# Sheet_3_nizovie.net
KiCad netlist of a schematic drawn in Altium Designer
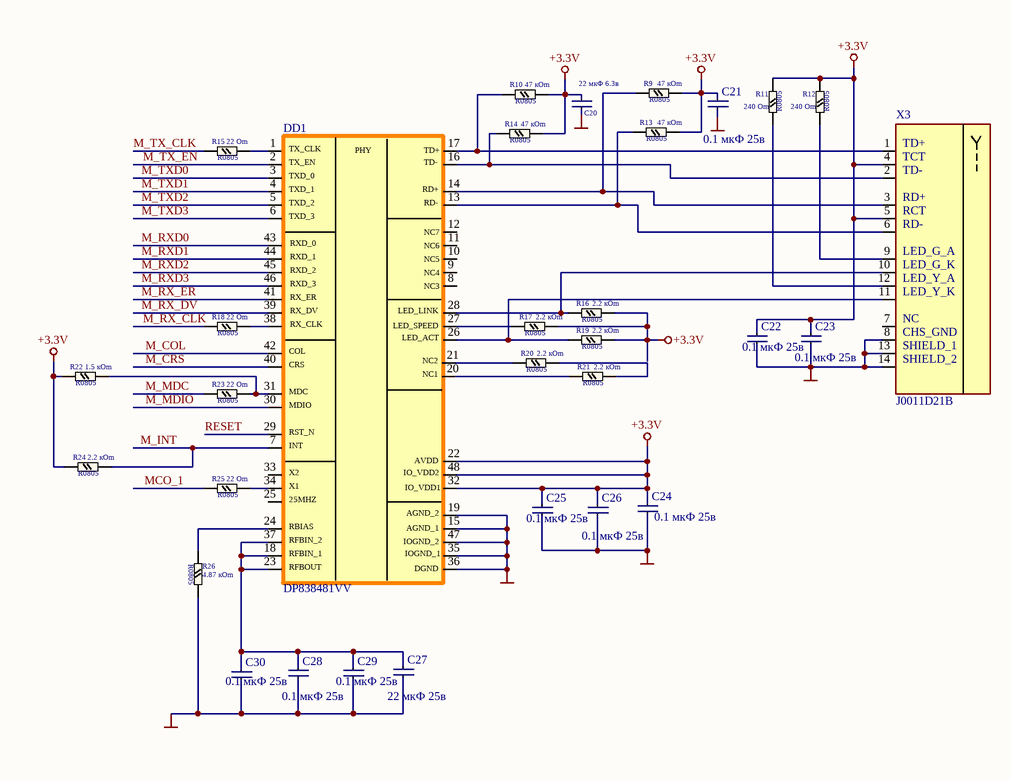
[diagram p0: Sheet_3_nizovie.SchDoc]

(export (version "E")
  (design (tool "Eeschema 10.0.6"))
  (components
    (comp (ref "C20")
      (value "22 мкФ 6.3в")
      (footprint "FP_0805")
      (libsource (lib "Schlib_nizovie") (part "C0805"))
    )
    (comp (ref "C21")
      (value "0.1 мкФ 25в")
      (footprint "FP_0805")
      (libsource (lib "Schlib_nizovie") (part "C0805"))
    )
    (comp (ref "C22")
      (value "0.1 мкФ 25в")
      (footprint "FP_0805")
      (libsource (lib "Schlib_nizovie") (part "C0805"))
    )
    (comp (ref "C23")
      (value "0.1 мкФ 25в")
      (footprint "FP_0805")
      (libsource (lib "Schlib_nizovie") (part "C0805"))
    )
    (comp (ref "C24")
      (value "0.1 мкФ 25в")
      (footprint "FP_0805")
      (libsource (lib "Schlib_nizovie") (part "C0805"))
    )
    (comp (ref "C25")
      (value "0.1 мкФ 25в")
      (footprint "FP_0805")
      (libsource (lib "Schlib_nizovie") (part "C0805"))
    )
    (comp (ref "C26")
      (value "0.1 мкФ 25в")
      (footprint "FP_0805")
      (libsource (lib "Schlib_nizovie") (part "C0805"))
    )
    (comp (ref "C27")
      (value "22 мкФ 25в")
      (footprint "FP_0805")
      (libsource (lib "Schlib_nizovie") (part "C0805"))
    )
    (comp (ref "C28")
      (value "0.1 мкФ 25в")
      (footprint "FP_0805")
      (libsource (lib "Schlib_nizovie") (part "C0805"))
    )
    (comp (ref "C29")
      (value "0.1 мкФ 25в")
      (footprint "FP_0805")
      (libsource (lib "Schlib_nizovie") (part "C0805"))
    )
    (comp (ref "C30")
      (value "0.1 мкФ 25в")
      (footprint "FP_0805")
      (libsource (lib "Schlib_nizovie") (part "C0805"))
    )
    (comp (ref "DD1")
      (value "DP838481VV")
      (footprint "TSQFP50P905X905X140-48N")
      (libsource (lib "Schlib_nizovie") (part "DP838481VV"))
    )
    (comp (ref "R9") (value "47 êÎm") (footprint "FP_0805") (libsource (lib "Schlib_nizovie") (part "R0805")))
    (comp (ref "R10")
      (value "47 êÎm")
      (footprint "FP_0805")
      (libsource (lib "Schlib_nizovie") (part "R0805"))
    )
    (comp (ref "R11") (value "240 Îm") (footprint "FP_0805") (libsource (lib "") (part "R0805_1")))
    (comp (ref "R12") (value "240 Îm") (footprint "FP_0805") (libsource (lib "") (part "R0805_1")))
    (comp (ref "R13")
      (value "47 êÎm")
      (footprint "FP_0805")
      (libsource (lib "Schlib_nizovie") (part "R0805"))
    )
    (comp (ref "R14")
      (value "47 êÎm")
      (footprint "FP_0805")
      (libsource (lib "Schlib_nizovie") (part "R0805"))
    )
    (comp (ref "R15") (value "22 Îm") (footprint "FP_0805") (libsource (lib "Schlib_nizovie") (part "R0805")))
    (comp (ref "R16")
      (value "2.2 êÎm")
      (footprint "FP_0805")
      (libsource (lib "Schlib_nizovie") (part "R0805"))
    )
    (comp (ref "R17")
      (value "2.2 êÎm")
      (footprint "FP_0805")
      (libsource (lib "Schlib_nizovie") (part "R0805"))
    )
    (comp (ref "R18") (value "22 Îm") (footprint "FP_0805") (libsource (lib "Schlib_nizovie") (part "R0805")))
    (comp (ref "R19")
      (value "2.2 êÎm")
      (footprint "FP_0805")
      (libsource (lib "Schlib_nizovie") (part "R0805"))
    )
    (comp (ref "R20")
      (value "2.2 êÎm")
      (footprint "FP_0805")
      (libsource (lib "Schlib_nizovie") (part "R0805"))
    )
    (comp (ref "R21")
      (value "2.2 êÎm")
      (footprint "FP_0805")
      (libsource (lib "Schlib_nizovie") (part "R0805"))
    )
    (comp (ref "R22")
      (value "1.5 êÎm")
      (footprint "FP_0805")
      (libsource (lib "Schlib_nizovie") (part "R0805"))
    )
    (comp (ref "R23") (value "22 Îm") (footprint "FP_0805") (libsource (lib "Schlib_nizovie") (part "R0805")))
    (comp (ref "R24")
      (value "2.2 êÎm")
      (footprint "FP_0805")
      (libsource (lib "Schlib_nizovie") (part "R0805"))
    )
    (comp (ref "R25") (value "22 Îm") (footprint "FP_0805") (libsource (lib "Schlib_nizovie") (part "R0805")))
    (comp (ref "R26") (value "4.87 êÎm") (footprint "FP_0805") (libsource (lib "") (part "R0805_2")))
    (comp (ref "X3")
      (value "J0011D21B")
      (footprint "J0006D21BNL")
      (libsource (lib "Schlib_nizovie") (part "J0011D21B"))
    )
  )
  (nets
    (net (code "1") (name "+3.3V") (class "Default")
      (node (ref "C20") (pin "2") (pinfunction "2_2") (pintype "passive"))
      (node (ref "C21") (pin "2") (pinfunction "2_2") (pintype "passive"))
      (node (ref "C22") (pin "2") (pinfunction "2_2") (pintype "passive"))
      (node (ref "C23") (pin "2") (pinfunction "2_2") (pintype "passive"))
      (node (ref "C24") (pin "2") (pinfunction "2_2") (pintype "passive"))
      (node (ref "C25") (pin "2") (pinfunction "2_2") (pintype "passive"))
      (node (ref "C26") (pin "2") (pinfunction "2_2") (pintype "passive"))
      (node (ref "DD1") (pin "22") (pinfunction "22_22") (pintype "passive"))
      (node (ref "DD1") (pin "32") (pinfunction "32_32") (pintype "passive"))
      (node (ref "DD1") (pin "48") (pinfunction "48_48") (pintype "passive"))
      (node (ref "R10") (pin "2") (pinfunction "2_2") (pintype "passive"))
      (node (ref "R11") (pin "2") (pinfunction "2_2") (pintype "passive"))
      (node (ref "R12") (pin "2") (pinfunction "2_2") (pintype "passive"))
      (node (ref "R13") (pin "2") (pinfunction "2_2") (pintype "passive"))
      (node (ref "R14") (pin "2") (pinfunction "2_2") (pintype "passive"))
      (node (ref "R16") (pin "2") (pinfunction "2_2") (pintype "passive"))
      (node (ref "R17") (pin "2") (pinfunction "2_2") (pintype "passive"))
      (node (ref "R19") (pin "2") (pinfunction "2_2") (pintype "passive"))
      (node (ref "R22") (pin "1") (pinfunction "1_1") (pintype "passive"))
      (node (ref "R24") (pin "1") (pinfunction "1_1") (pintype "passive"))
      (node (ref "R9") (pin "2") (pinfunction "2_2") (pintype "passive"))
      (node (ref "X3") (pin "4") (pinfunction "4_4") (pintype "passive"))
      (node (ref "X3") (pin "5") (pinfunction "5_5") (pintype "passive"))
    )
    (net (code "2") (name "/MCO_1") (class "Default")
      (node (ref "R25") (pin "1") (pinfunction "1_1") (pintype "passive"))
    )
    (net (code "3") (name "/M_COL") (class "Default")
      (node (ref "DD1") (pin "42") (pinfunction "42_42") (pintype "passive"))
    )
    (net (code "4") (name "/M_CRS") (class "Default")
      (node (ref "DD1") (pin "40") (pinfunction "40_40") (pintype "passive"))
    )
    (net (code "5") (name "/M_INT") (class "Default")
      (node (ref "DD1") (pin "7") (pinfunction "7_7") (pintype "passive"))
      (node (ref "R24") (pin "2") (pinfunction "2_2") (pintype "passive"))
    )
    (net (code "6") (name "/M_MDC") (class "Default")
      (node (ref "R23") (pin "1") (pinfunction "1_1") (pintype "passive"))
    )
    (net (code "7") (name "/M_MDIO") (class "Default")
      (node (ref "DD1") (pin "30") (pinfunction "30_30") (pintype "passive"))
    )
    (net (code "8") (name "/M_RXD0") (class "Default")
      (node (ref "DD1") (pin "43") (pinfunction "43_43") (pintype "passive"))
    )
    (net (code "9") (name "/M_RXD1") (class "Default")
      (node (ref "DD1") (pin "44") (pinfunction "44_44") (pintype "passive"))
    )
    (net (code "10") (name "/M_RXD2") (class "Default")
      (node (ref "DD1") (pin "45") (pinfunction "45_45") (pintype "passive"))
    )
    (net (code "11") (name "/M_RXD3") (class "Default")
      (node (ref "DD1") (pin "46") (pinfunction "46_46") (pintype "passive"))
    )
    (net (code "12") (name "/M_RX_CLK") (class "Default")
      (node (ref "R18") (pin "1") (pinfunction "1_1") (pintype "passive"))
    )
    (net (code "13") (name "/M_RX_DV") (class "Default")
      (node (ref "DD1") (pin "39") (pinfunction "39_39") (pintype "passive"))
    )
    (net (code "14") (name "/M_RX_ER") (class "Default")
      (node (ref "DD1") (pin "41") (pinfunction "41_41") (pintype "passive"))
    )
    (net (code "15") (name "/M_TXD0") (class "Default")
      (node (ref "DD1") (pin "3") (pinfunction "3_3") (pintype "passive"))
    )
    (net (code "16") (name "/M_TXD1") (class "Default")
      (node (ref "DD1") (pin "4") (pinfunction "4_4") (pintype "passive"))
    )
    (net (code "17") (name "/M_TXD2") (class "Default")
      (node (ref "DD1") (pin "5") (pinfunction "5_5") (pintype "passive"))
    )
    (net (code "18") (name "/M_TXD3") (class "Default")
      (node (ref "DD1") (pin "6") (pinfunction "6_6") (pintype "passive"))
    )
    (net (code "19") (name "/M_TX_CLK") (class "Default")
      (node (ref "R15") (pin "1") (pinfunction "1_1") (pintype "passive"))
    )
    (net (code "20") (name "/M_TX_EN") (class "Default")
      (node (ref "DD1") (pin "2") (pinfunction "2_2") (pintype "passive"))
    )
    (net (code "21") (name "/RESET") (class "Default")
      (node (ref "DD1") (pin "29") (pinfunction "29_29") (pintype "passive"))
    )
    (net (code "22") (name "GND") (class "Default")
      (node (ref "C20") (pin "1") (pinfunction "1_1") (pintype "passive"))
      (node (ref "C21") (pin "1") (pinfunction "1_1") (pintype "passive"))
      (node (ref "C22") (pin "1") (pinfunction "1_1") (pintype "passive"))
      (node (ref "C23") (pin "1") (pinfunction "1_1") (pintype "passive"))
      (node (ref "C24") (pin "1") (pinfunction "1_1") (pintype "passive"))
      (node (ref "C25") (pin "1") (pinfunction "1_1") (pintype "passive"))
      (node (ref "C26") (pin "1") (pinfunction "1_1") (pintype "passive"))
      (node (ref "C27") (pin "1") (pinfunction "1_1") (pintype "passive"))
      (node (ref "C28") (pin "1") (pinfunction "1_1") (pintype "passive"))
      (node (ref "C29") (pin "1") (pinfunction "1_1") (pintype "passive"))
      (node (ref "C30") (pin "1") (pinfunction "1_1") (pintype "passive"))
      (node (ref "DD1") (pin "15") (pinfunction "15_15") (pintype "passive"))
      (node (ref "DD1") (pin "19") (pinfunction "19_19") (pintype "passive"))
      (node (ref "DD1") (pin "35") (pinfunction "35_35") (pintype "passive"))
      (node (ref "DD1") (pin "36") (pinfunction "36_36") (pintype "passive"))
      (node (ref "DD1") (pin "47") (pinfunction "47_47") (pintype "passive"))
      (node (ref "R26") (pin "2") (pinfunction "2_2") (pintype "passive"))
      (node (ref "X3") (pin "13") (pinfunction "13_13") (pintype "passive"))
      (node (ref "X3") (pin "14") (pinfunction "14_14") (pintype "passive"))
      (node (ref "X3") (pin "8") (pinfunction "8_8") (pintype "passive"))
    )
    (net (code "23") (name "Net-(C27-Pad2)") (class "Default")
      (node (ref "C27") (pin "2") (pinfunction "2_2") (pintype "passive"))
      (node (ref "C28") (pin "2") (pinfunction "2_2") (pintype "passive"))
      (node (ref "C29") (pin "2") (pinfunction "2_2") (pintype "passive"))
      (node (ref "C30") (pin "2") (pinfunction "2_2") (pintype "passive"))
      (node (ref "DD1") (pin "18") (pinfunction "18_18") (pintype "passive"))
      (node (ref "DD1") (pin "23") (pinfunction "23_23") (pintype "passive"))
      (node (ref "DD1") (pin "37") (pinfunction "37_37") (pintype "passive"))
    )
    (net (code "24") (name "Net-(DD1-Pad1)") (class "Default")
      (node (ref "DD1") (pin "1") (pinfunction "1_1") (pintype "passive"))
      (node (ref "R15") (pin "2") (pinfunction "2_2") (pintype "passive"))
    )
    (net (code "25") (name "Net-(DD1-Pad13)") (class "Default")
      (node (ref "DD1") (pin "13") (pinfunction "13_13") (pintype "passive"))
      (node (ref "R13") (pin "1") (pinfunction "1_1") (pintype "passive"))
      (node (ref "X3") (pin "6") (pinfunction "6_6") (pintype "passive"))
    )
    (net (code "26") (name "Net-(DD1-Pad14)") (class "Default")
      (node (ref "DD1") (pin "14") (pinfunction "14_14") (pintype "passive"))
      (node (ref "R9") (pin "1") (pinfunction "1_1") (pintype "passive"))
      (node (ref "X3") (pin "3") (pinfunction "3_3") (pintype "passive"))
    )
    (net (code "27") (name "Net-(DD1-Pad16)") (class "Default")
      (node (ref "DD1") (pin "16") (pinfunction "16_16") (pintype "passive"))
      (node (ref "R14") (pin "1") (pinfunction "1_1") (pintype "passive"))
      (node (ref "X3") (pin "2") (pinfunction "2_2") (pintype "passive"))
    )
    (net (code "28") (name "Net-(DD1-Pad17)") (class "Default")
      (node (ref "DD1") (pin "17") (pinfunction "17_17") (pintype "passive"))
      (node (ref "R10") (pin "1") (pinfunction "1_1") (pintype "passive"))
      (node (ref "X3") (pin "1") (pinfunction "1_1") (pintype "passive"))
    )
    (net (code "29") (name "Net-(DD1-Pad20)") (class "Default")
      (node (ref "DD1") (pin "20") (pinfunction "20_20") (pintype "passive"))
      (node (ref "R21") (pin "1") (pinfunction "1_1") (pintype "passive"))
    )
    (net (code "30") (name "Net-(DD1-Pad21)") (class "Default")
      (node (ref "DD1") (pin "21") (pinfunction "21_21") (pintype "passive"))
      (node (ref "R20") (pin "1") (pinfunction "1_1") (pintype "passive"))
    )
    (net (code "31") (name "Net-(DD1-Pad24)") (class "Default")
      (node (ref "DD1") (pin "24") (pinfunction "24_24") (pintype "passive"))
      (node (ref "R26") (pin "1") (pinfunction "1_1") (pintype "passive"))
    )
    (net (code "32") (name "Net-(DD1-Pad26)") (class "Default")
      (node (ref "DD1") (pin "26") (pinfunction "26_26") (pintype "passive"))
      (node (ref "R19") (pin "1") (pinfunction "1_1") (pintype "passive"))
      (node (ref "X3") (pin "11") (pinfunction "11_11") (pintype "passive"))
    )
    (net (code "33") (name "Net-(DD1-Pad27)") (class "Default")
      (node (ref "DD1") (pin "27") (pinfunction "27_27") (pintype "passive"))
      (node (ref "R17") (pin "1") (pinfunction "1_1") (pintype "passive"))
    )
    (net (code "34") (name "Net-(DD1-Pad28)") (class "Default")
      (node (ref "DD1") (pin "28") (pinfunction "28_28") (pintype "passive"))
      (node (ref "R16") (pin "1") (pinfunction "1_1") (pintype "passive"))
      (node (ref "X3") (pin "10") (pinfunction "10_10") (pintype "passive"))
    )
    (net (code "35") (name "Net-(DD1-Pad31)") (class "Default")
      (node (ref "DD1") (pin "31") (pinfunction "31_31") (pintype "passive"))
      (node (ref "R22") (pin "2") (pinfunction "2_2") (pintype "passive"))
      (node (ref "R23") (pin "2") (pinfunction "2_2") (pintype "passive"))
    )
    (net (code "36") (name "Net-(DD1-Pad34)") (class "Default")
      (node (ref "DD1") (pin "34") (pinfunction "34_34") (pintype "passive"))
      (node (ref "R25") (pin "2") (pinfunction "2_2") (pintype "passive"))
    )
    (net (code "37") (name "Net-(DD1-Pad38)") (class "Default")
      (node (ref "DD1") (pin "38") (pinfunction "38_38") (pintype "passive"))
      (node (ref "R18") (pin "2") (pinfunction "2_2") (pintype "passive"))
    )
    (net (code "38") (name "Net-(R11-Pad1)") (class "Default")
      (node (ref "R11") (pin "1") (pinfunction "1_1") (pintype "passive"))
      (node (ref "X3") (pin "12") (pinfunction "12_12") (pintype "passive"))
    )
    (net (code "39") (name "Net-(R12-Pad1)") (class "Default")
      (node (ref "R12") (pin "1") (pinfunction "1_1") (pintype "passive"))
      (node (ref "X3") (pin "9") (pinfunction "9_9") (pintype "passive"))
    )
    (net (code "40") (name "Net-(R20-Pad2)") (class "Default")
      (node (ref "R20") (pin "2") (pinfunction "2_2") (pintype "passive"))
      (node (ref "R21") (pin "2") (pinfunction "2_2") (pintype "passive"))
    )
    (net (code "41") (name "unconnected-(DD1-Pad8)") (class "Default")
      (node (ref "DD1") (pin "8") (pinfunction "8_8") (pintype "passive"))
    )
    (net (code "42") (name "unconnected-(DD1-Pad9)") (class "Default")
      (node (ref "DD1") (pin "9") (pinfunction "9_9") (pintype "passive"))
    )
    (net (code "43") (name "unconnected-(DD1-Pad10)") (class "Default")
      (node (ref "DD1") (pin "10") (pinfunction "10_10") (pintype "passive"))
    )
    (net (code "44") (name "unconnected-(DD1-Pad11)") (class "Default")
      (node (ref "DD1") (pin "11") (pinfunction "11_11") (pintype "passive"))
    )
    (net (code "45") (name "unconnected-(DD1-Pad12)") (class "Default")
      (node (ref "DD1") (pin "12") (pinfunction "12_12") (pintype "passive"))
    )
    (net (code "46") (name "unconnected-(DD1-Pad25)") (class "Default")
      (node (ref "DD1") (pin "25") (pinfunction "25_25") (pintype "passive"))
    )
    (net (code "47") (name "unconnected-(DD1-Pad33)") (class "Default")
      (node (ref "DD1") (pin "33") (pinfunction "33_33") (pintype "passive"))
    )
    (net (code "48") (name "unconnected-(X3-Pad7)") (class "Default")
      (node (ref "X3") (pin "7") (pinfunction "7_7") (pintype "passive"))
    )
  )
)
